# UM220_NEO-M8.net
KiCad netlist of a schematic drawn in Altium Designer
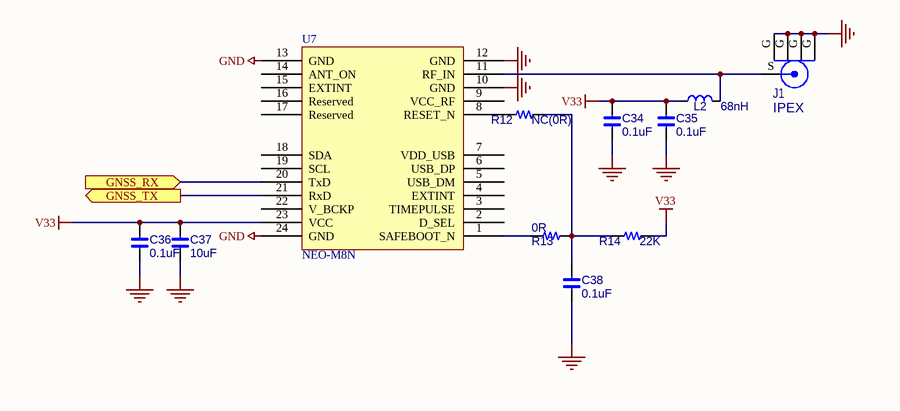
[diagram p0: UM220 NEO-M8.SchDoc]

(export (version "E")
  (design (tool "Eeschema 10.0.6"))
  (components
    (comp (ref "C34")
      (value "0.1uF")
      (footprint "0402CAPC1005X06N")
      (description "C")
      (libsource (lib "YxmSCH") (part "C"))
    )
    (comp (ref "C35")
      (value "0.1uF")
      (footprint "0402CAPC1005X06N")
      (description "C")
      (libsource (lib "YxmSCH") (part "C"))
    )
    (comp (ref "C36")
      (value "0.1uF")
      (footprint "0402CAPC1005X06N")
      (description "C")
      (libsource (lib "YxmSCH") (part "C"))
    )
    (comp (ref "C37")
      (value "10uF")
      (footprint "0603CAPC1608X09N")
      (description "C")
      (libsource (lib "YxmSCH") (part "C"))
    )
    (comp (ref "C38")
      (value "0.1uF")
      (footprint "0402CAPC1005X06N")
      (description "C")
      (libsource (lib "YxmSCH") (part "C"))
    )
    (comp (ref "J1")
      (value "IPEX")
      (footprint "IPEX")
      (description "RF Connector")
      (fields (field (name "PUBLISHER") "ChenTao"))
      (libsource (lib "THTF_SCHLIB_V1P0_20130724") (part "RF Connector"))
    )
    (comp (ref "L2")
      (value "68nH")
      (footprint "0402RESC1005X04N")
      (description "L")
      (libsource (lib "Schlib_20130101") (part "L"))
    )
    (comp (ref "R12")
      (value "NC(0R)")
      (footprint "0402RESC1005X04N")
      (description "R")
      (libsource (lib "Schlib_20130101") (part "R"))
    )
    (comp (ref "R13")
      (value "0R")
      (footprint "0402RESC1005X04N")
      (description "R")
      (libsource (lib "Schlib_20130101") (part "R"))
    )
    (comp (ref "R14")
      (value "22K")
      (footprint "0402RESC1005X04N")
      (description "R")
      (libsource (lib "Schlib_20130101") (part "R"))
    )
    (comp (ref "U7")
      (value "NEO-M8N")
      (footprint "UM220")
      (libsource (lib "Schlib_20130601") (part "NEO-M8N"))
    )
  )
  (nets
    (net (code "1") (name "/GNSS_RX") (class "Default")
      (node (ref "U7") (pin "20") (pinfunction "TxD_20") (pintype "passive"))
    )
    (net (code "2") (name "/GNSS_TX") (class "Default")
      (node (ref "U7") (pin "21") (pinfunction "RxD_21") (pintype "passive"))
    )
    (net (code "3") (name "GND") (class "Default")
      (node (ref "C34") (pin "2") (pintype "passive"))
      (node (ref "C35") (pin "2") (pintype "passive"))
      (node (ref "C36") (pin "2") (pintype "passive"))
      (node (ref "C37") (pin "2") (pintype "passive"))
      (node (ref "C38") (pin "2") (pintype "passive"))
      (node (ref "J1") (pin "G") (pinfunction "Ground_G") (pintype "passive"))
      (node (ref "U7") (pin "10") (pinfunction "GND_10") (pintype "passive"))
      (node (ref "U7") (pin "12") (pinfunction "GND_12") (pintype "passive"))
      (node (ref "U7") (pin "13") (pinfunction "GND_13") (pintype "passive"))
      (node (ref "U7") (pin "24") (pinfunction "GND_24") (pintype "passive"))
    )
    (net (code "4") (name "Net-(C38-Pad1)") (class "Default")
      (node (ref "C38") (pin "1") (pintype "passive"))
      (node (ref "R12") (pin "2") (pintype "passive"))
      (node (ref "R13") (pin "2") (pintype "passive"))
      (node (ref "R14") (pin "1") (pintype "passive"))
    )
    (net (code "5") (name "Net-(J1-Signal)") (class "Default")
      (node (ref "J1") (pin "S") (pinfunction "Signal_S") (pintype "passive"))
      (node (ref "L2") (pin "2") (pintype "passive"))
      (node (ref "U7") (pin "11") (pinfunction "RF_IN_11") (pintype "passive"))
    )
    (net (code "6") (name "Net-(U7-RESET_N)") (class "Default")
      (node (ref "R12") (pin "1") (pintype "passive"))
      (node (ref "U7") (pin "8") (pinfunction "RESET_N_8") (pintype "passive"))
    )
    (net (code "7") (name "Net-(U7-SAFEBOOT_N)") (class "Default")
      (node (ref "R13") (pin "1") (pintype "passive"))
      (node (ref "U7") (pin "1") (pinfunction "SAFEBOOT_N_1") (pintype "passive"))
    )
    (net (code "8") (name "V33") (class "Default")
      (node (ref "C34") (pin "1") (pintype "passive"))
      (node (ref "C35") (pin "1") (pintype "passive"))
      (node (ref "C36") (pin "1") (pintype "passive"))
      (node (ref "C37") (pin "1") (pintype "passive"))
      (node (ref "L2") (pin "1") (pintype "passive"))
      (node (ref "R14") (pin "2") (pintype "passive"))
      (node (ref "U7") (pin "23") (pinfunction "VCC_23") (pintype "passive"))
    )
    (net (code "9") (name "unconnected-(U7-ANT_ON-Pad14)") (class "Default")
      (node (ref "U7") (pin "14") (pinfunction "ANT_ON_14") (pintype "passive"))
    )
    (net (code "10") (name "unconnected-(U7-D_SEL-Pad2)") (class "Default")
      (node (ref "U7") (pin "2") (pinfunction "D_SEL_2") (pintype "passive"))
    )
    (net (code "11") (name "unconnected-(U7-EXTINT-Pad4)") (class "Default")
      (node (ref "U7") (pin "4") (pinfunction "EXTINT_4") (pintype "passive"))
    )
    (net (code "12") (name "unconnected-(U7-EXTINT-Pad15)") (class "Default")
      (node (ref "U7") (pin "15") (pinfunction "EXTINT_15") (pintype "passive"))
    )
    (net (code "13") (name "unconnected-(U7-Reserved-Pad16)") (class "Default")
      (node (ref "U7") (pin "16") (pinfunction "Reserved_16") (pintype "passive"))
    )
    (net (code "14") (name "unconnected-(U7-Reserved-Pad17)") (class "Default")
      (node (ref "U7") (pin "17") (pinfunction "Reserved_17") (pintype "passive"))
    )
    (net (code "15") (name "unconnected-(U7-SCL-Pad19)") (class "Default")
      (node (ref "U7") (pin "19") (pinfunction "SCL_19") (pintype "passive"))
    )
    (net (code "16") (name "unconnected-(U7-SDA-Pad18)") (class "Default")
      (node (ref "U7") (pin "18") (pinfunction "SDA_18") (pintype "passive"))
    )
    (net (code "17") (name "unconnected-(U7-TIMEPULSE-Pad3)") (class "Default")
      (node (ref "U7") (pin "3") (pinfunction "TIMEPULSE_3") (pintype "passive"))
    )
    (net (code "18") (name "unconnected-(U7-USB_DM-Pad5)") (class "Default")
      (node (ref "U7") (pin "5") (pinfunction "USB_DM_5") (pintype "passive"))
    )
    (net (code "19") (name "unconnected-(U7-USB_DP-Pad6)") (class "Default")
      (node (ref "U7") (pin "6") (pinfunction "USB_DP_6") (pintype "passive"))
    )
    (net (code "20") (name "unconnected-(U7-VCC_RF-Pad9)") (class "Default")
      (node (ref "U7") (pin "9") (pinfunction "VCC_RF_9") (pintype "passive"))
    )
    (net (code "21") (name "unconnected-(U7-VDD_USB-Pad7)") (class "Default")
      (node (ref "U7") (pin "7") (pinfunction "VDD_USB_7") (pintype "passive"))
    )
    (net (code "22") (name "unconnected-(U7-V_BCKP-Pad22)") (class "Default")
      (node (ref "U7") (pin "22") (pinfunction "V_BCKP_22") (pintype "passive"))
    )
  )
)
